# 00_Overview.net
KiCad netlist of a schematic drawn in Altium Designer
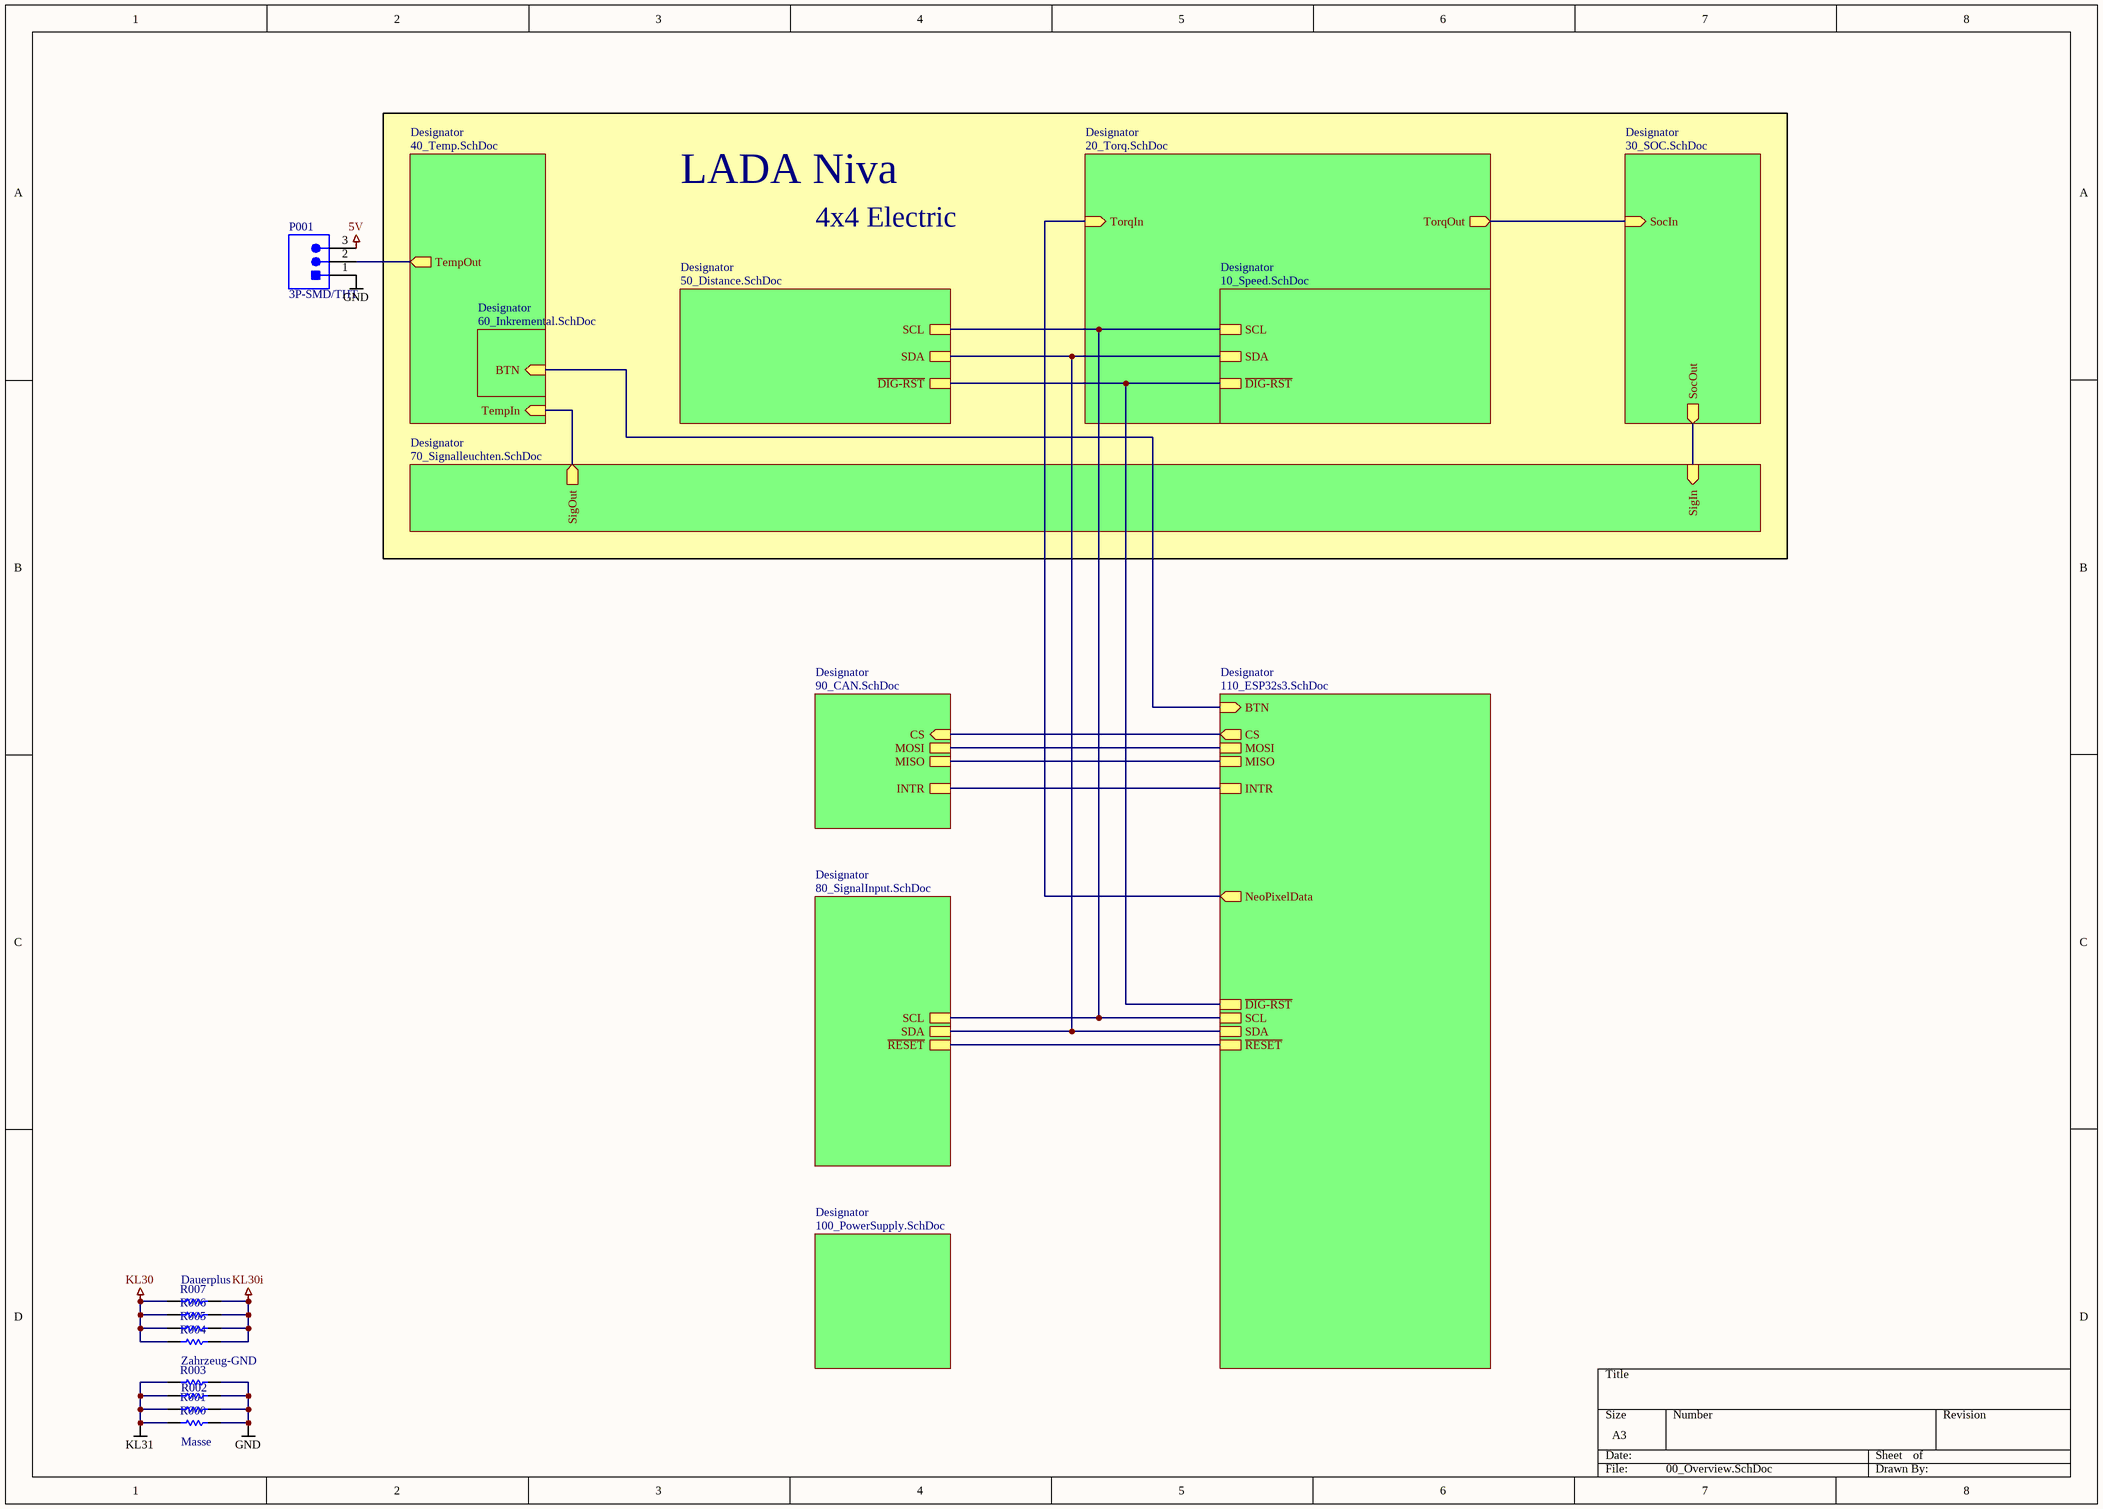
[diagram p0: 00_Overview.SchDoc]

(export (version "E")
  (design (tool "Eeschema 10.0.6"))
  (components
    (comp (ref "P001")
      (value "3P-SMD/THT")
      (footprint "3P-SMD/THT")
      (libsource (lib "AltiumLib_MILUTIN") (part "3P-SMD/THT"))
    )
    (comp (ref "R000")
      (value "RC0603JR-070RL")
      (footprint "RESC1608X55X25ML10T15")
      (description "Chip Resistor, 0 Ohm, +/- 5%, 0.1 W, -55 to 155 degC, 0603 (1608 Metric), RoHS, Tape and Reel")
      (fields (field (name "TOLERANCE") "5%") (field (name "MANUFACTURER") "Yageo"))
      (libsource (lib "Altium Content Vault") (part "RES-2"))
    )
    (comp (ref "R001")
      (value "RC0603JR-070RL")
      (footprint "RESC1608X55X25ML10T15")
      (description "Chip Resistor, 0 Ohm, +/- 5%, 0.1 W, -55 to 155 degC, 0603 (1608 Metric), RoHS, Tape and Reel")
      (fields (field (name "TOLERANCE") "5%") (field (name "MANUFACTURER") "Yageo"))
      (libsource (lib "Altium Content Vault") (part "RES-2"))
    )
    (comp (ref "R002")
      (value "RC0603JR-070RL")
      (footprint "RESC1608X55X25ML10T15")
      (description "Chip Resistor, 0 Ohm, +/- 5%, 0.1 W, -55 to 155 degC, 0603 (1608 Metric), RoHS, Tape and Reel")
      (fields (field (name "TOLERANCE") "5%") (field (name "MANUFACTURER") "Yageo"))
      (libsource (lib "Altium Content Vault") (part "RES-2"))
    )
    (comp (ref "R003")
      (value "RC0603JR-070RL")
      (footprint "RESC1608X55X25ML10T15")
      (description "Chip Resistor, 0 Ohm, +/- 5%, 0.1 W, -55 to 155 degC, 0603 (1608 Metric), RoHS, Tape and Reel")
      (fields (field (name "TOLERANCE") "5%") (field (name "MANUFACTURER") "Yageo"))
      (libsource (lib "Altium Content Vault") (part "RES-2"))
    )
    (comp (ref "R004")
      (value "RC0603JR-070RL")
      (footprint "RESC1608X55X25ML10T15")
      (description "Chip Resistor, 0 Ohm, +/- 5%, 0.1 W, -55 to 155 degC, 0603 (1608 Metric), RoHS, Tape and Reel")
      (fields (field (name "TOLERANCE") "5%") (field (name "MANUFACTURER") "Yageo"))
      (libsource (lib "Altium Content Vault") (part "RES-2"))
    )
    (comp (ref "R005")
      (value "RC0603JR-070RL")
      (footprint "RESC1608X55X25ML10T15")
      (description "Chip Resistor, 0 Ohm, +/- 5%, 0.1 W, -55 to 155 degC, 0603 (1608 Metric), RoHS, Tape and Reel")
      (fields (field (name "TOLERANCE") "5%") (field (name "MANUFACTURER") "Yageo"))
      (libsource (lib "Altium Content Vault") (part "RES-2"))
    )
    (comp (ref "R006")
      (value "RC0603JR-070RL")
      (footprint "RESC1608X55X25ML10T15")
      (description "Chip Resistor, 0 Ohm, +/- 5%, 0.1 W, -55 to 155 degC, 0603 (1608 Metric), RoHS, Tape and Reel")
      (fields (field (name "TOLERANCE") "5%") (field (name "MANUFACTURER") "Yageo"))
      (libsource (lib "Altium Content Vault") (part "RES-2"))
    )
    (comp (ref "R007")
      (value "RC0603JR-070RL")
      (footprint "RESC1608X55X25ML10T15")
      (description "Chip Resistor, 0 Ohm, +/- 5%, 0.1 W, -55 to 155 degC, 0603 (1608 Metric), RoHS, Tape and Reel")
      (fields (field (name "TOLERANCE") "5%") (field (name "MANUFACTURER") "Yageo"))
      (libsource (lib "Altium Content Vault") (part "RES-2"))
    )
  )
  (nets
    (net (code "11") (name "/TempOut") (class "Default")
      (node (ref "P001") (pin "2") (pinfunction "2_2") (pintype "passive"))
    )
    (net (code "15") (name "5V") (class "Default")
      (node (ref "P001") (pin "3") (pinfunction "3_3") (pintype "passive"))
    )
    (net (code "16") (name "GND") (class "Default")
      (node (ref "P001") (pin "1") (pinfunction "1_1") (pintype "passive"))
      (node (ref "R000") (pin "2") (pinfunction "2_2") (pintype "passive"))
      (node (ref "R001") (pin "2") (pinfunction "2_2") (pintype "passive"))
      (node (ref "R002") (pin "2") (pinfunction "2_2") (pintype "passive"))
      (node (ref "R003") (pin "2") (pinfunction "2_2") (pintype "passive"))
    )
    (net (code "17") (name "KL30") (class "Default")
      (node (ref "R004") (pin "1") (pinfunction "1_1") (pintype "passive"))
      (node (ref "R005") (pin "1") (pinfunction "1_1") (pintype "passive"))
      (node (ref "R006") (pin "1") (pinfunction "1_1") (pintype "passive"))
      (node (ref "R007") (pin "1") (pinfunction "1_1") (pintype "passive"))
    )
    (net (code "18") (name "KL30i") (class "Default")
      (node (ref "R004") (pin "2") (pinfunction "2_2") (pintype "passive"))
      (node (ref "R005") (pin "2") (pinfunction "2_2") (pintype "passive"))
      (node (ref "R006") (pin "2") (pinfunction "2_2") (pintype "passive"))
      (node (ref "R007") (pin "2") (pinfunction "2_2") (pintype "passive"))
    )
    (net (code "19") (name "KL31") (class "Default")
      (node (ref "R000") (pin "1") (pinfunction "1_1") (pintype "passive"))
      (node (ref "R001") (pin "1") (pinfunction "1_1") (pintype "passive"))
      (node (ref "R002") (pin "1") (pinfunction "1_1") (pintype "passive"))
      (node (ref "R003") (pin "1") (pinfunction "1_1") (pintype "passive"))
    )
  )
)
